# Phased_Array_Ant.net
KiCad netlist of a schematic drawn in EAGLE
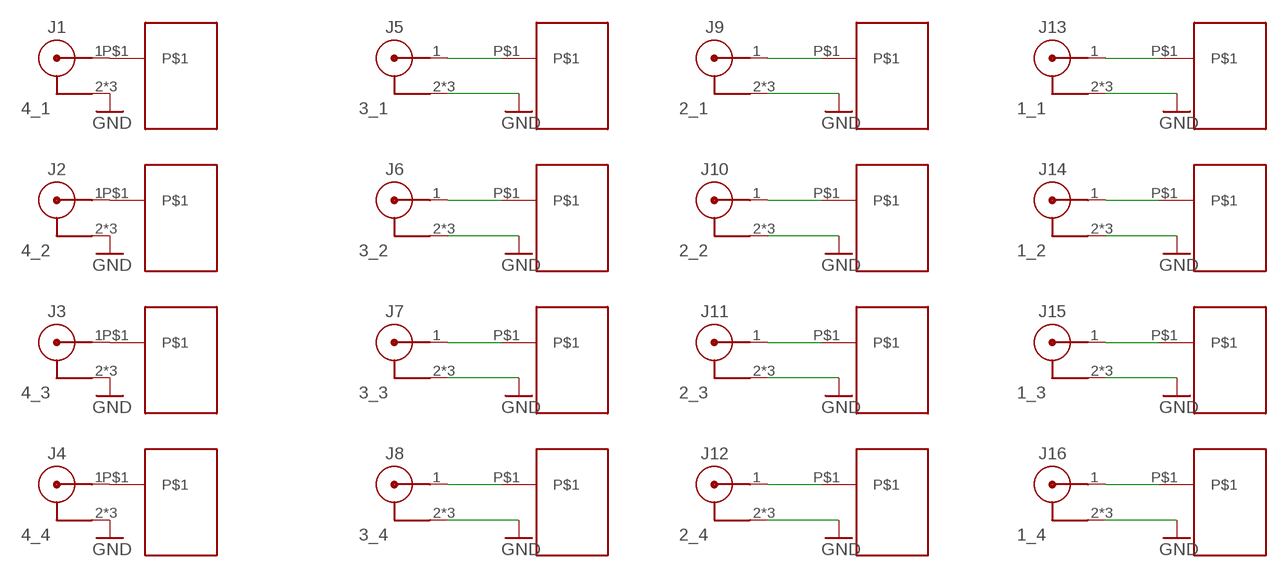
[diagram p0: schematic, sheet 1]

(export (version "E")
  (design (tool "Eeschema 10.0.6"))
  (components
    (comp (ref "J1")
      (value "4_1")
      (footprint "eagle-import:60124102122403")
      (libsource (lib "eagle-import") (part "60124102122403"))
    )
    (comp (ref "J2")
      (value "4_2")
      (footprint "eagle-import:60124102122403")
      (libsource (lib "eagle-import") (part "60124102122403"))
    )
    (comp (ref "J3")
      (value "4_3")
      (footprint "eagle-import:60124102122403")
      (libsource (lib "eagle-import") (part "60124102122403"))
    )
    (comp (ref "J4")
      (value "4_4")
      (footprint "eagle-import:60124102122403")
      (libsource (lib "eagle-import") (part "60124102122403"))
    )
    (comp (ref "J5")
      (value "3_1")
      (footprint "eagle-import:60124102122403")
      (libsource (lib "eagle-import") (part "60124102122403"))
    )
    (comp (ref "J6")
      (value "3_2")
      (footprint "eagle-import:60124102122403")
      (libsource (lib "eagle-import") (part "60124102122403"))
    )
    (comp (ref "J7")
      (value "3_3")
      (footprint "eagle-import:60124102122403")
      (libsource (lib "eagle-import") (part "60124102122403"))
    )
    (comp (ref "J8")
      (value "3_4")
      (footprint "eagle-import:60124102122403")
      (libsource (lib "eagle-import") (part "60124102122403"))
    )
    (comp (ref "J9")
      (value "2_1")
      (footprint "eagle-import:60124102122403")
      (libsource (lib "eagle-import") (part "60124102122403"))
    )
    (comp (ref "J10")
      (value "2_2")
      (footprint "eagle-import:60124102122403")
      (libsource (lib "eagle-import") (part "60124102122403"))
    )
    (comp (ref "J11")
      (value "2_3")
      (footprint "eagle-import:60124102122403")
      (libsource (lib "eagle-import") (part "60124102122403"))
    )
    (comp (ref "J12")
      (value "2_4")
      (footprint "eagle-import:60124102122403")
      (libsource (lib "eagle-import") (part "60124102122403"))
    )
    (comp (ref "J13")
      (value "1_1")
      (footprint "eagle-import:60124102122403")
      (libsource (lib "eagle-import") (part "60124102122403"))
    )
    (comp (ref "J14")
      (value "1_2")
      (footprint "eagle-import:60124102122403")
      (libsource (lib "eagle-import") (part "60124102122403"))
    )
    (comp (ref "J15")
      (value "1_3")
      (footprint "eagle-import:60124102122403")
      (libsource (lib "eagle-import") (part "60124102122403"))
    )
    (comp (ref "J16")
      (value "1_4")
      (footprint "eagle-import:60124102122403")
      (libsource (lib "eagle-import") (part "60124102122403"))
    )
    (comp (ref "U$1")
      (value "10.5GHZ_ANT")
      (footprint "eagle-import:10.5GHZ_ANT")
      (libsource (lib "eagle-import") (part "10.5GHZ_ANT"))
    )
    (comp (ref "U$2")
      (value "10.5GHZ_ANT")
      (footprint "eagle-import:10.5GHZ_ANT")
      (libsource (lib "eagle-import") (part "10.5GHZ_ANT"))
    )
    (comp (ref "U$3")
      (value "10.5GHZ_ANT")
      (footprint "eagle-import:10.5GHZ_ANT")
      (libsource (lib "eagle-import") (part "10.5GHZ_ANT"))
    )
    (comp (ref "U$4")
      (value "10.5GHZ_ANT")
      (footprint "eagle-import:10.5GHZ_ANT")
      (libsource (lib "eagle-import") (part "10.5GHZ_ANT"))
    )
    (comp (ref "U$5")
      (value "10.5GHZ_ANT")
      (footprint "eagle-import:10.5GHZ_ANT")
      (libsource (lib "eagle-import") (part "10.5GHZ_ANT"))
    )
    (comp (ref "U$6")
      (value "10.5GHZ_ANT")
      (footprint "eagle-import:10.5GHZ_ANT")
      (libsource (lib "eagle-import") (part "10.5GHZ_ANT"))
    )
    (comp (ref "U$7")
      (value "10.5GHZ_ANT")
      (footprint "eagle-import:10.5GHZ_ANT")
      (libsource (lib "eagle-import") (part "10.5GHZ_ANT"))
    )
    (comp (ref "U$8")
      (value "10.5GHZ_ANT")
      (footprint "eagle-import:10.5GHZ_ANT")
      (libsource (lib "eagle-import") (part "10.5GHZ_ANT"))
    )
    (comp (ref "U$9")
      (value "10.5GHZ_ANT")
      (footprint "eagle-import:10.5GHZ_ANT")
      (libsource (lib "eagle-import") (part "10.5GHZ_ANT"))
    )
    (comp (ref "U$10")
      (value "10.5GHZ_ANT")
      (footprint "eagle-import:10.5GHZ_ANT")
      (libsource (lib "eagle-import") (part "10.5GHZ_ANT"))
    )
    (comp (ref "U$11")
      (value "10.5GHZ_ANT")
      (footprint "eagle-import:10.5GHZ_ANT")
      (libsource (lib "eagle-import") (part "10.5GHZ_ANT"))
    )
    (comp (ref "U$12")
      (value "10.5GHZ_ANT")
      (footprint "eagle-import:10.5GHZ_ANT")
      (libsource (lib "eagle-import") (part "10.5GHZ_ANT"))
    )
    (comp (ref "U$13")
      (value "10.5GHZ_ANT")
      (footprint "eagle-import:10.5GHZ_ANT")
      (libsource (lib "eagle-import") (part "10.5GHZ_ANT"))
    )
    (comp (ref "U$14")
      (value "10.5GHZ_ANT")
      (footprint "eagle-import:10.5GHZ_ANT")
      (libsource (lib "eagle-import") (part "10.5GHZ_ANT"))
    )
    (comp (ref "U$15")
      (value "10.5GHZ_ANT")
      (footprint "eagle-import:10.5GHZ_ANT")
      (libsource (lib "eagle-import") (part "10.5GHZ_ANT"))
    )
    (comp (ref "U$16")
      (value "10.5GHZ_ANT")
      (footprint "eagle-import:10.5GHZ_ANT")
      (libsource (lib "eagle-import") (part "10.5GHZ_ANT"))
    )
  )
  (nets
    (net (code "1") (name "GND") (class "Default")
      (node (ref "J1") (pin "2") (pinfunction "2_2") (pintype "passive"))
      (node (ref "J1") (pin "3") (pinfunction "2_3") (pintype "passive"))
      (node (ref "J1") (pin "4") (pinfunction "2_4") (pintype "passive"))
      (node (ref "J10") (pin "2") (pinfunction "2_2") (pintype "passive"))
      (node (ref "J10") (pin "3") (pinfunction "2_3") (pintype "passive"))
      (node (ref "J10") (pin "4") (pinfunction "2_4") (pintype "passive"))
      (node (ref "J11") (pin "2") (pinfunction "2_2") (pintype "passive"))
      (node (ref "J11") (pin "3") (pinfunction "2_3") (pintype "passive"))
      (node (ref "J11") (pin "4") (pinfunction "2_4") (pintype "passive"))
      (node (ref "J12") (pin "2") (pinfunction "2_2") (pintype "passive"))
      (node (ref "J12") (pin "3") (pinfunction "2_3") (pintype "passive"))
      (node (ref "J12") (pin "4") (pinfunction "2_4") (pintype "passive"))
      (node (ref "J13") (pin "2") (pinfunction "2_2") (pintype "passive"))
      (node (ref "J13") (pin "3") (pinfunction "2_3") (pintype "passive"))
      (node (ref "J13") (pin "4") (pinfunction "2_4") (pintype "passive"))
      (node (ref "J14") (pin "2") (pinfunction "2_2") (pintype "passive"))
      (node (ref "J14") (pin "3") (pinfunction "2_3") (pintype "passive"))
      (node (ref "J14") (pin "4") (pinfunction "2_4") (pintype "passive"))
      (node (ref "J15") (pin "2") (pinfunction "2_2") (pintype "passive"))
      (node (ref "J15") (pin "3") (pinfunction "2_3") (pintype "passive"))
      (node (ref "J15") (pin "4") (pinfunction "2_4") (pintype "passive"))
      (node (ref "J16") (pin "2") (pinfunction "2_2") (pintype "passive"))
      (node (ref "J16") (pin "3") (pinfunction "2_3") (pintype "passive"))
      (node (ref "J16") (pin "4") (pinfunction "2_4") (pintype "passive"))
      (node (ref "J2") (pin "2") (pinfunction "2_2") (pintype "passive"))
      (node (ref "J2") (pin "3") (pinfunction "2_3") (pintype "passive"))
      (node (ref "J2") (pin "4") (pinfunction "2_4") (pintype "passive"))
      (node (ref "J3") (pin "2") (pinfunction "2_2") (pintype "passive"))
      (node (ref "J3") (pin "3") (pinfunction "2_3") (pintype "passive"))
      (node (ref "J3") (pin "4") (pinfunction "2_4") (pintype "passive"))
      (node (ref "J4") (pin "2") (pinfunction "2_2") (pintype "passive"))
      (node (ref "J4") (pin "3") (pinfunction "2_3") (pintype "passive"))
      (node (ref "J4") (pin "4") (pinfunction "2_4") (pintype "passive"))
      (node (ref "J5") (pin "2") (pinfunction "2_2") (pintype "passive"))
      (node (ref "J5") (pin "3") (pinfunction "2_3") (pintype "passive"))
      (node (ref "J5") (pin "4") (pinfunction "2_4") (pintype "passive"))
      (node (ref "J6") (pin "2") (pinfunction "2_2") (pintype "passive"))
      (node (ref "J6") (pin "3") (pinfunction "2_3") (pintype "passive"))
      (node (ref "J6") (pin "4") (pinfunction "2_4") (pintype "passive"))
      (node (ref "J7") (pin "2") (pinfunction "2_2") (pintype "passive"))
      (node (ref "J7") (pin "3") (pinfunction "2_3") (pintype "passive"))
      (node (ref "J7") (pin "4") (pinfunction "2_4") (pintype "passive"))
      (node (ref "J8") (pin "2") (pinfunction "2_2") (pintype "passive"))
      (node (ref "J8") (pin "3") (pinfunction "2_3") (pintype "passive"))
      (node (ref "J8") (pin "4") (pinfunction "2_4") (pintype "passive"))
      (node (ref "J9") (pin "2") (pinfunction "2_2") (pintype "passive"))
      (node (ref "J9") (pin "3") (pinfunction "2_3") (pintype "passive"))
      (node (ref "J9") (pin "4") (pinfunction "2_4") (pintype "passive"))
    )
    (net (code "2") (name "Net-(J1-Pad1)") (class "Default")
      (node (ref "J1") (pin "1") (pinfunction "1_1") (pintype "passive"))
      (node (ref "U$1") (pin "P$1") (pinfunction "P$1_P$1") (pintype "bidirectional"))
    )
    (net (code "3") (name "Net-(J2-Pad1)") (class "Default")
      (node (ref "J2") (pin "1") (pinfunction "1_1") (pintype "passive"))
      (node (ref "U$2") (pin "P$1") (pinfunction "P$1_P$1") (pintype "bidirectional"))
    )
    (net (code "4") (name "Net-(J3-Pad1)") (class "Default")
      (node (ref "J3") (pin "1") (pinfunction "1_1") (pintype "passive"))
      (node (ref "U$3") (pin "P$1") (pinfunction "P$1_P$1") (pintype "bidirectional"))
    )
    (net (code "5") (name "Net-(J4-Pad1)") (class "Default")
      (node (ref "J4") (pin "1") (pinfunction "1_1") (pintype "passive"))
      (node (ref "U$4") (pin "P$1") (pinfunction "P$1_P$1") (pintype "bidirectional"))
    )
    (net (code "6") (name "Net-(J5-Pad1)") (class "Default")
      (node (ref "J5") (pin "1") (pinfunction "1_1") (pintype "passive"))
      (node (ref "U$5") (pin "P$1") (pinfunction "P$1_P$1") (pintype "bidirectional"))
    )
    (net (code "7") (name "Net-(J6-Pad1)") (class "Default")
      (node (ref "J6") (pin "1") (pinfunction "1_1") (pintype "passive"))
      (node (ref "U$6") (pin "P$1") (pinfunction "P$1_P$1") (pintype "bidirectional"))
    )
    (net (code "8") (name "Net-(J7-Pad1)") (class "Default")
      (node (ref "J7") (pin "1") (pinfunction "1_1") (pintype "passive"))
      (node (ref "U$7") (pin "P$1") (pinfunction "P$1_P$1") (pintype "bidirectional"))
    )
    (net (code "9") (name "Net-(J8-Pad1)") (class "Default")
      (node (ref "J8") (pin "1") (pinfunction "1_1") (pintype "passive"))
      (node (ref "U$8") (pin "P$1") (pinfunction "P$1_P$1") (pintype "bidirectional"))
    )
    (net (code "10") (name "Net-(J9-Pad1)") (class "Default")
      (node (ref "J9") (pin "1") (pinfunction "1_1") (pintype "passive"))
      (node (ref "U$9") (pin "P$1") (pinfunction "P$1_P$1") (pintype "bidirectional"))
    )
    (net (code "11") (name "Net-(J10-Pad1)") (class "Default")
      (node (ref "J10") (pin "1") (pinfunction "1_1") (pintype "passive"))
      (node (ref "U$10") (pin "P$1") (pinfunction "P$1_P$1") (pintype "bidirectional"))
    )
    (net (code "12") (name "Net-(J11-Pad1)") (class "Default")
      (node (ref "J11") (pin "1") (pinfunction "1_1") (pintype "passive"))
      (node (ref "U$11") (pin "P$1") (pinfunction "P$1_P$1") (pintype "bidirectional"))
    )
    (net (code "13") (name "Net-(J12-Pad1)") (class "Default")
      (node (ref "J12") (pin "1") (pinfunction "1_1") (pintype "passive"))
      (node (ref "U$12") (pin "P$1") (pinfunction "P$1_P$1") (pintype "bidirectional"))
    )
    (net (code "14") (name "Net-(J13-Pad1)") (class "Default")
      (node (ref "J13") (pin "1") (pinfunction "1_1") (pintype "passive"))
      (node (ref "U$13") (pin "P$1") (pinfunction "P$1_P$1") (pintype "bidirectional"))
    )
    (net (code "15") (name "Net-(J14-Pad1)") (class "Default")
      (node (ref "J14") (pin "1") (pinfunction "1_1") (pintype "passive"))
      (node (ref "U$14") (pin "P$1") (pinfunction "P$1_P$1") (pintype "bidirectional"))
    )
    (net (code "16") (name "Net-(J15-Pad1)") (class "Default")
      (node (ref "J15") (pin "1") (pinfunction "1_1") (pintype "passive"))
      (node (ref "U$15") (pin "P$1") (pinfunction "P$1_P$1") (pintype "bidirectional"))
    )
    (net (code "17") (name "Net-(J16-Pad1)") (class "Default")
      (node (ref "J16") (pin "1") (pinfunction "1_1") (pintype "passive"))
      (node (ref "U$16") (pin "P$1") (pinfunction "P$1_P$1") (pintype "bidirectional"))
    )
  )
)
